# sashwat-mc-one-smd.net
KiCad netlist of a schematic drawn in EAGLE
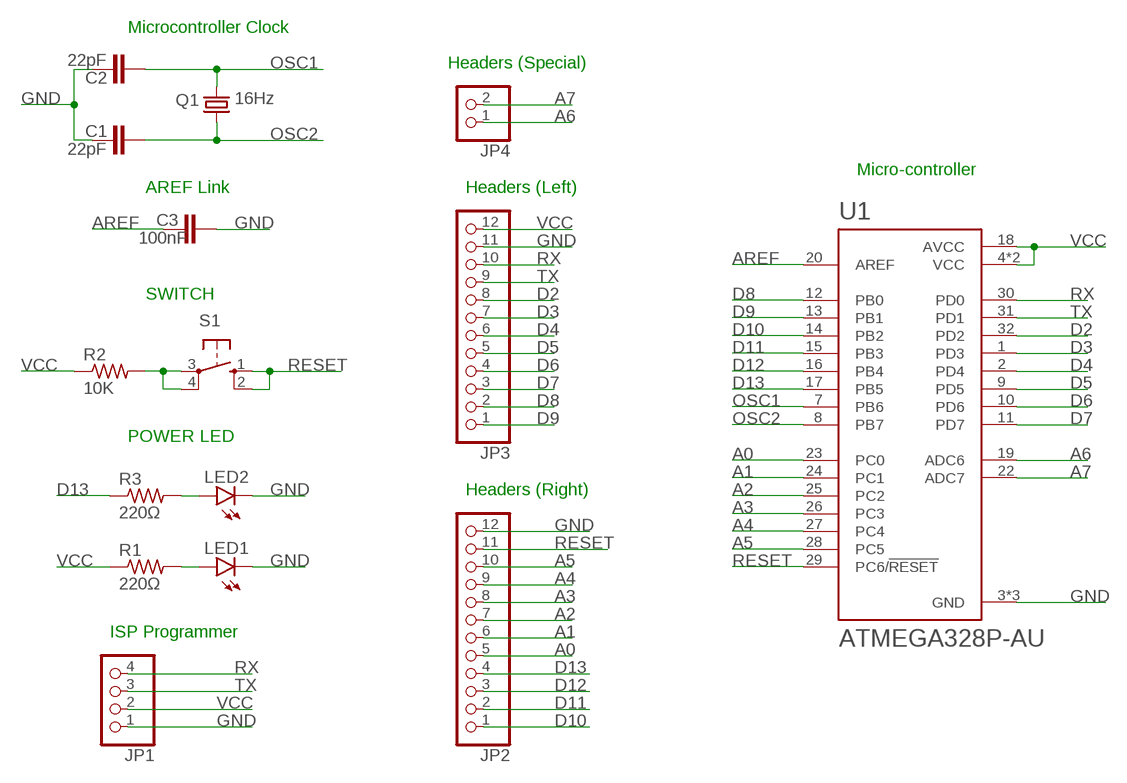
[diagram p0: schematic, sheet 1]

(export (version "E")
  (design (tool "Eeschema 10.0.6"))
  (components
    (comp (ref "C1")
      (value "22pF")
      (footprint "eagle-import:C0805")
      (libsource (lib "eagle-import") (part "C-EUC0805"))
    )
    (comp (ref "C2")
      (value "22pF")
      (footprint "eagle-import:C0805")
      (libsource (lib "eagle-import") (part "C-EUC0805"))
    )
    (comp (ref "C3")
      (value "100nF")
      (footprint "eagle-import:C0805")
      (libsource (lib "eagle-import") (part "C-EUC0805"))
    )
    (comp (ref "JP1")
      (value "PINHD-1X4")
      (footprint "eagle-import:1X04")
      (libsource (lib "eagle-import") (part "PINHD-1X4"))
    )
    (comp (ref "JP2")
      (value "PINHD-1X12")
      (footprint "eagle-import:1X12")
      (libsource (lib "eagle-import") (part "PINHD-1X12"))
    )
    (comp (ref "JP3")
      (value "PINHD-1X12")
      (footprint "eagle-import:1X12")
      (libsource (lib "eagle-import") (part "PINHD-1X12"))
    )
    (comp (ref "JP4")
      (value "PINHD-1X2")
      (footprint "eagle-import:1X02")
      (libsource (lib "eagle-import") (part "PINHD-1X2"))
    )
    (comp (ref "LED1")
      (value "LEDCHIPLED_0805")
      (footprint "eagle-import:CHIPLED_0805")
      (libsource (lib "eagle-import") (part "LEDCHIPLED_0805"))
    )
    (comp (ref "LED2")
      (value "LEDCHIPLED_0805")
      (footprint "eagle-import:CHIPLED_0805")
      (libsource (lib "eagle-import") (part "LEDCHIPLED_0805"))
    )
    (comp (ref "Q1")
      (value "16Hz")
      (footprint "eagle-import:HC49_S")
      (libsource (lib "eagle-import") (part "CRYSTALHC49S"))
    )
    (comp (ref "R1")
      (value "220Ω")
      (footprint "eagle-import:R0805")
      (libsource (lib "eagle-import") (part "R-US_R0805"))
    )
    (comp (ref "R2")
      (value "10K")
      (footprint "eagle-import:R0805")
      (libsource (lib "eagle-import") (part "R-US_R0805"))
    )
    (comp (ref "R3")
      (value "220Ω")
      (footprint "eagle-import:R0805")
      (libsource (lib "eagle-import") (part "R-US_R0805"))
    )
    (comp (ref "S1")
      (value "10-XX")
      (footprint "eagle-import:B3F-10XX")
      (fields (field (name "MPN") "B3F-1000"))
      (libsource (lib "eagle-import") (part "10-XX"))
    )
    (comp (ref "U1")
      (value "ATMEGA328P-AU")
      (footprint "eagle-import:QFP80P900X900X120-32N")
      (fields (field (name "MF") "Microchip Technology"))
      (libsource (lib "eagle-import") (part "ATMEGA328P-AU"))
    )
  )
  (nets
    (net (code "1") (name "/A0") (class "Default")
      (node (ref "JP2") (pin "5") (pinfunction "5_5") (pintype "passive"))
      (node (ref "U1") (pin "23") (pinfunction "PC0_23") (pintype "bidirectional"))
    )
    (net (code "2") (name "/A1") (class "Default")
      (node (ref "JP2") (pin "6") (pinfunction "6_6") (pintype "passive"))
      (node (ref "U1") (pin "24") (pinfunction "PC1_24") (pintype "bidirectional"))
    )
    (net (code "3") (name "/A2") (class "Default")
      (node (ref "JP2") (pin "7") (pinfunction "7_7") (pintype "passive"))
      (node (ref "U1") (pin "25") (pinfunction "PC2_25") (pintype "bidirectional"))
    )
    (net (code "4") (name "/A3") (class "Default")
      (node (ref "JP2") (pin "8") (pinfunction "8_8") (pintype "passive"))
      (node (ref "U1") (pin "26") (pinfunction "PC3_26") (pintype "bidirectional"))
    )
    (net (code "5") (name "/A4") (class "Default")
      (node (ref "JP2") (pin "9") (pinfunction "9_9") (pintype "passive"))
      (node (ref "U1") (pin "27") (pinfunction "PC4_27") (pintype "bidirectional"))
    )
    (net (code "6") (name "/A5") (class "Default")
      (node (ref "JP2") (pin "10") (pinfunction "10_10") (pintype "passive"))
      (node (ref "U1") (pin "28") (pinfunction "PC5_28") (pintype "bidirectional"))
    )
    (net (code "7") (name "/A6") (class "Default")
      (node (ref "JP4") (pin "1") (pinfunction "1_1") (pintype "passive"))
      (node (ref "U1") (pin "19") (pinfunction "ADC6_19") (pintype "bidirectional"))
    )
    (net (code "8") (name "/A7") (class "Default")
      (node (ref "JP4") (pin "2") (pinfunction "2_2") (pintype "passive"))
      (node (ref "U1") (pin "22") (pinfunction "ADC7_22") (pintype "bidirectional"))
    )
    (net (code "9") (name "/AREF") (class "Default")
      (node (ref "C3") (pin "2") (pinfunction "2_2") (pintype "passive"))
      (node (ref "U1") (pin "20") (pinfunction "AREF_20") (pintype "input"))
    )
    (net (code "10") (name "/D2") (class "Default")
      (node (ref "JP3") (pin "8") (pinfunction "8_8") (pintype "passive"))
      (node (ref "U1") (pin "32") (pinfunction "PD2_32") (pintype "bidirectional"))
    )
    (net (code "11") (name "/D3") (class "Default")
      (node (ref "JP3") (pin "7") (pinfunction "7_7") (pintype "passive"))
      (node (ref "U1") (pin "1") (pinfunction "PD3_1") (pintype "bidirectional"))
    )
    (net (code "12") (name "/D4") (class "Default")
      (node (ref "JP3") (pin "6") (pinfunction "6_6") (pintype "passive"))
      (node (ref "U1") (pin "2") (pinfunction "PD4_2") (pintype "bidirectional"))
    )
    (net (code "13") (name "/D5") (class "Default")
      (node (ref "JP3") (pin "5") (pinfunction "5_5") (pintype "passive"))
      (node (ref "U1") (pin "9") (pinfunction "PD5_9") (pintype "bidirectional"))
    )
    (net (code "14") (name "/D6") (class "Default")
      (node (ref "JP3") (pin "4") (pinfunction "4_4") (pintype "passive"))
      (node (ref "U1") (pin "10") (pinfunction "PD6_10") (pintype "bidirectional"))
    )
    (net (code "15") (name "/D7") (class "Default")
      (node (ref "JP3") (pin "3") (pinfunction "3_3") (pintype "passive"))
      (node (ref "U1") (pin "11") (pinfunction "PD7_11") (pintype "bidirectional"))
    )
    (net (code "16") (name "/D8") (class "Default")
      (node (ref "JP3") (pin "2") (pinfunction "2_2") (pintype "passive"))
      (node (ref "U1") (pin "12") (pinfunction "PB0_12") (pintype "bidirectional"))
    )
    (net (code "17") (name "/D9") (class "Default")
      (node (ref "JP3") (pin "1") (pinfunction "1_1") (pintype "passive"))
      (node (ref "U1") (pin "13") (pinfunction "PB1_13") (pintype "bidirectional"))
    )
    (net (code "18") (name "/D10") (class "Default")
      (node (ref "JP2") (pin "1") (pinfunction "1_1") (pintype "passive"))
      (node (ref "U1") (pin "14") (pinfunction "PB2_14") (pintype "bidirectional"))
    )
    (net (code "19") (name "/D11") (class "Default")
      (node (ref "JP2") (pin "2") (pinfunction "2_2") (pintype "passive"))
      (node (ref "U1") (pin "15") (pinfunction "PB3_15") (pintype "bidirectional"))
    )
    (net (code "20") (name "/D12") (class "Default")
      (node (ref "JP2") (pin "3") (pinfunction "3_3") (pintype "passive"))
      (node (ref "U1") (pin "16") (pinfunction "PB4_16") (pintype "bidirectional"))
    )
    (net (code "21") (name "/D13") (class "Default")
      (node (ref "JP2") (pin "4") (pinfunction "4_4") (pintype "passive"))
      (node (ref "R3") (pin "1") (pinfunction "1_1") (pintype "passive"))
      (node (ref "U1") (pin "17") (pinfunction "PB5_17") (pintype "bidirectional"))
    )
    (net (code "22") (name "/GND") (class "Default")
      (node (ref "C1") (pin "2") (pinfunction "2_2") (pintype "passive"))
      (node (ref "C2") (pin "2") (pinfunction "2_2") (pintype "passive"))
      (node (ref "C3") (pin "1") (pinfunction "1_1") (pintype "passive"))
      (node (ref "JP1") (pin "1") (pinfunction "1_1") (pintype "passive"))
      (node (ref "JP2") (pin "12") (pinfunction "12_12") (pintype "passive"))
      (node (ref "JP3") (pin "11") (pinfunction "11_11") (pintype "passive"))
      (node (ref "LED1") (pin "C") (pinfunction "C_C") (pintype "passive"))
      (node (ref "LED2") (pin "C") (pinfunction "C_C") (pintype "passive"))
      (node (ref "U1") (pin "21") (pinfunction "GND_21") (pintype "power_in"))
      (node (ref "U1") (pin "3") (pinfunction "GND_3") (pintype "power_in"))
      (node (ref "U1") (pin "5") (pinfunction "GND_5") (pintype "power_in"))
    )
    (net (code "23") (name "/OSC1") (class "Default")
      (node (ref "C2") (pin "1") (pinfunction "1_1") (pintype "passive"))
      (node (ref "Q1") (pin "2") (pinfunction "2_2") (pintype "passive"))
      (node (ref "U1") (pin "7") (pinfunction "PB6_7") (pintype "bidirectional"))
    )
    (net (code "24") (name "/OSC2") (class "Default")
      (node (ref "C1") (pin "1") (pinfunction "1_1") (pintype "passive"))
      (node (ref "Q1") (pin "1") (pinfunction "1_1") (pintype "passive"))
      (node (ref "U1") (pin "8") (pinfunction "PB7_8") (pintype "bidirectional"))
    )
    (net (code "25") (name "/RESET") (class "Default")
      (node (ref "JP2") (pin "11") (pinfunction "11_11") (pintype "passive"))
      (node (ref "S1") (pin "1") (pinfunction "S_1") (pintype "passive"))
      (node (ref "S1") (pin "2") (pinfunction "S1_2") (pintype "passive"))
      (node (ref "U1") (pin "29") (pinfunction "PC6/~{RESET}_29") (pintype "bidirectional"))
    )
    (net (code "26") (name "/RX") (class "Default")
      (node (ref "JP1") (pin "4") (pinfunction "4_4") (pintype "passive"))
      (node (ref "JP3") (pin "10") (pinfunction "10_10") (pintype "passive"))
      (node (ref "U1") (pin "30") (pinfunction "PD0_30") (pintype "bidirectional"))
    )
    (net (code "27") (name "/TX") (class "Default")
      (node (ref "JP1") (pin "3") (pinfunction "3_3") (pintype "passive"))
      (node (ref "JP3") (pin "9") (pinfunction "9_9") (pintype "passive"))
      (node (ref "U1") (pin "31") (pinfunction "PD1_31") (pintype "bidirectional"))
    )
    (net (code "28") (name "/VCC") (class "Default")
      (node (ref "JP1") (pin "2") (pinfunction "2_2") (pintype "passive"))
      (node (ref "JP3") (pin "12") (pinfunction "12_12") (pintype "passive"))
      (node (ref "R1") (pin "1") (pinfunction "1_1") (pintype "passive"))
      (node (ref "R2") (pin "1") (pinfunction "1_1") (pintype "passive"))
      (node (ref "U1") (pin "18") (pinfunction "AVCC_18") (pintype "power_in"))
      (node (ref "U1") (pin "4") (pinfunction "VCC_4") (pintype "power_in"))
      (node (ref "U1") (pin "6") (pinfunction "VCC_6") (pintype "power_in"))
    )
    (net (code "29") (name "Net-(LED1-PadA)") (class "Default")
      (node (ref "LED1") (pin "A") (pinfunction "A_A") (pintype "passive"))
      (node (ref "R1") (pin "2") (pinfunction "2_2") (pintype "passive"))
    )
    (net (code "30") (name "Net-(LED2-PadA)") (class "Default")
      (node (ref "LED2") (pin "A") (pinfunction "A_A") (pintype "passive"))
      (node (ref "R3") (pin "2") (pinfunction "2_2") (pintype "passive"))
    )
    (net (code "31") (name "Net-(S1-P)") (class "Default")
      (node (ref "R2") (pin "2") (pinfunction "2_2") (pintype "passive"))
      (node (ref "S1") (pin "3") (pinfunction "P_3") (pintype "passive"))
      (node (ref "S1") (pin "4") (pinfunction "P1_4") (pintype "passive"))
    )
  )
)
